# MidWifi.net
KiCad netlist of a schematic drawn in Altium Designer
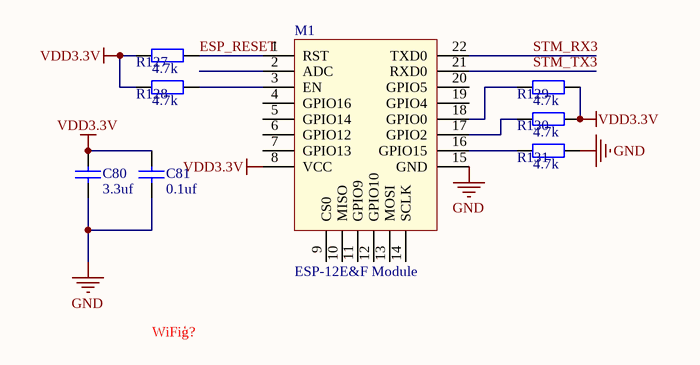
[diagram p0: MidWifi.SchDoc]

(export (version "E")
  (design (tool "Eeschema 10.0.6"))
  (components
    (comp (ref "C80")
      (value "3.3uf")
      (footprint "C0805")
      (description "Capacitor")
      (fields
        (field (name "MANUFACTURER") "Generic Components")
        (field (name "Comment") "Cap")
        (field (name "PUBLISHER") "Altium Hobart Technology Centre")
      )
      (libsource (lib "Miscellaneous Devices") (part "Cap"))
    )
    (comp (ref "C81")
      (value "0.1uf")
      (footprint "C0805")
      (description "Capacitor")
      (fields
        (field (name "MANUFACTURER") "Generic Components")
        (field (name "Comment") "Cap")
        (field (name "PUBLISHER") "Altium Hobart Technology Centre")
      )
      (libsource (lib "Miscellaneous Devices") (part "Cap"))
    )
    (comp (ref "M1")
      (value "ESP-12E&F Module")
      (footprint "ESP-12E&F Module")
      (libsource (lib "ESP-12E&F Module") (part "ESP-12E&F Module"))
    )
    (comp (ref "R127")
      (value "4.7k")
      (footprint "0805")
      (fields (field (name "Comment") "Res2"))
      (libsource (lib "S1") (part "RES"))
    )
    (comp (ref "R128")
      (value "4.7k")
      (footprint "0805")
      (fields (field (name "Comment") "Res2"))
      (libsource (lib "S1") (part "RES"))
    )
    (comp (ref "R129")
      (value "4.7k")
      (footprint "0805")
      (fields (field (name "Comment") "Res2"))
      (libsource (lib "S1") (part "RES"))
    )
    (comp (ref "R130")
      (value "4.7k")
      (footprint "0805")
      (fields (field (name "Comment") "Res2"))
      (libsource (lib "S1") (part "RES"))
    )
    (comp (ref "R131")
      (value "4.7k")
      (footprint "0805")
      (fields (field (name "Comment") "Res2"))
      (libsource (lib "S1") (part "RES"))
    )
  )
  (nets
    (net (code "1") (name "/ESP_RESET") (class "Default")
      (node (ref "M1") (pin "1") (pinfunction "RST_1") (pintype "passive"))
      (node (ref "R127") (pin "1") (pinfunction "1_1") (pintype "passive"))
    )
    (net (code "2") (name "/STM_RX3") (class "Default")
      (node (ref "M1") (pin "22") (pinfunction "TXD0_22") (pintype "passive"))
    )
    (net (code "3") (name "/STM_TX3") (class "Default")
      (node (ref "M1") (pin "21") (pinfunction "RXD0_21") (pintype "passive"))
    )
    (net (code "4") (name "GND") (class "Default")
      (node (ref "C80") (pin "2") (pinfunction "2_2") (pintype "passive"))
      (node (ref "C81") (pin "2") (pinfunction "2_2") (pintype "passive"))
      (node (ref "M1") (pin "15") (pinfunction "GND_15") (pintype "passive"))
      (node (ref "R131") (pin "1") (pinfunction "1_1") (pintype "passive"))
    )
    (net (code "5") (name "Net-(M1-EN)") (class "Default")
      (node (ref "M1") (pin "3") (pinfunction "EN_3") (pintype "passive"))
      (node (ref "R128") (pin "1") (pinfunction "1_1") (pintype "passive"))
    )
    (net (code "6") (name "Net-(M1-GPIO0)") (class "Default")
      (node (ref "M1") (pin "18") (pinfunction "GPIO0_18") (pintype "passive"))
      (node (ref "R129") (pin "2") (pinfunction "2_2") (pintype "passive"))
    )
    (net (code "7") (name "Net-(M1-GPIO2)") (class "Default")
      (node (ref "M1") (pin "17") (pinfunction "GPIO2_17") (pintype "passive"))
      (node (ref "R130") (pin "2") (pinfunction "2_2") (pintype "passive"))
    )
    (net (code "8") (name "Net-(M1-GPIO15)") (class "Default")
      (node (ref "M1") (pin "16") (pinfunction "GPIO15_16") (pintype "passive"))
      (node (ref "R131") (pin "2") (pinfunction "2_2") (pintype "passive"))
    )
    (net (code "9") (name "VDD3.3V") (class "Default")
      (node (ref "C80") (pin "1") (pinfunction "1_1") (pintype "passive"))
      (node (ref "C81") (pin "1") (pinfunction "1_1") (pintype "passive"))
      (node (ref "M1") (pin "8") (pinfunction "VCC_8") (pintype "passive"))
      (node (ref "R127") (pin "2") (pinfunction "2_2") (pintype "passive"))
      (node (ref "R128") (pin "2") (pinfunction "2_2") (pintype "passive"))
      (node (ref "R129") (pin "1") (pinfunction "1_1") (pintype "passive"))
      (node (ref "R130") (pin "1") (pinfunction "1_1") (pintype "passive"))
    )
    (net (code "10") (name "unconnected-(M1-ADC-Pad2)") (class "Default")
      (node (ref "M1") (pin "2") (pinfunction "ADC_2") (pintype "passive"))
    )
    (net (code "11") (name "unconnected-(M1-CS0-Pad9)") (class "Default")
      (node (ref "M1") (pin "9") (pinfunction "CS0_9") (pintype "passive"))
    )
    (net (code "12") (name "unconnected-(M1-GPIO4-Pad19)") (class "Default")
      (node (ref "M1") (pin "19") (pinfunction "GPIO4_19") (pintype "passive"))
    )
    (net (code "13") (name "unconnected-(M1-GPIO5-Pad20)") (class "Default")
      (node (ref "M1") (pin "20") (pinfunction "GPIO5_20") (pintype "passive"))
    )
    (net (code "14") (name "unconnected-(M1-GPIO9-Pad11)") (class "Default")
      (node (ref "M1") (pin "11") (pinfunction "GPIO9_11") (pintype "passive"))
    )
    (net (code "15") (name "unconnected-(M1-GPIO10-Pad12)") (class "Default")
      (node (ref "M1") (pin "12") (pinfunction "GPIO10_12") (pintype "passive"))
    )
    (net (code "16") (name "unconnected-(M1-GPIO12-Pad6)") (class "Default")
      (node (ref "M1") (pin "6") (pinfunction "GPIO12_6") (pintype "passive"))
    )
    (net (code "17") (name "unconnected-(M1-GPIO13-Pad7)") (class "Default")
      (node (ref "M1") (pin "7") (pinfunction "GPIO13_7") (pintype "passive"))
    )
    (net (code "18") (name "unconnected-(M1-GPIO14-Pad5)") (class "Default")
      (node (ref "M1") (pin "5") (pinfunction "GPIO14_5") (pintype "passive"))
    )
    (net (code "19") (name "unconnected-(M1-GPIO16-Pad4)") (class "Default")
      (node (ref "M1") (pin "4") (pinfunction "GPIO16_4") (pintype "passive"))
    )
    (net (code "20") (name "unconnected-(M1-MISO-Pad10)") (class "Default")
      (node (ref "M1") (pin "10") (pinfunction "MISO_10") (pintype "passive"))
    )
    (net (code "21") (name "unconnected-(M1-MOSI-Pad13)") (class "Default")
      (node (ref "M1") (pin "13") (pinfunction "MOSI_13") (pintype "passive"))
    )
    (net (code "22") (name "unconnected-(M1-SCLK-Pad14)") (class "Default")
      (node (ref "M1") (pin "14") (pinfunction "SCLK_14") (pintype "passive"))
    )
  )
)
